# battery_buzzer_changes.net
KiCad netlist of a schematic drawn in EAGLE
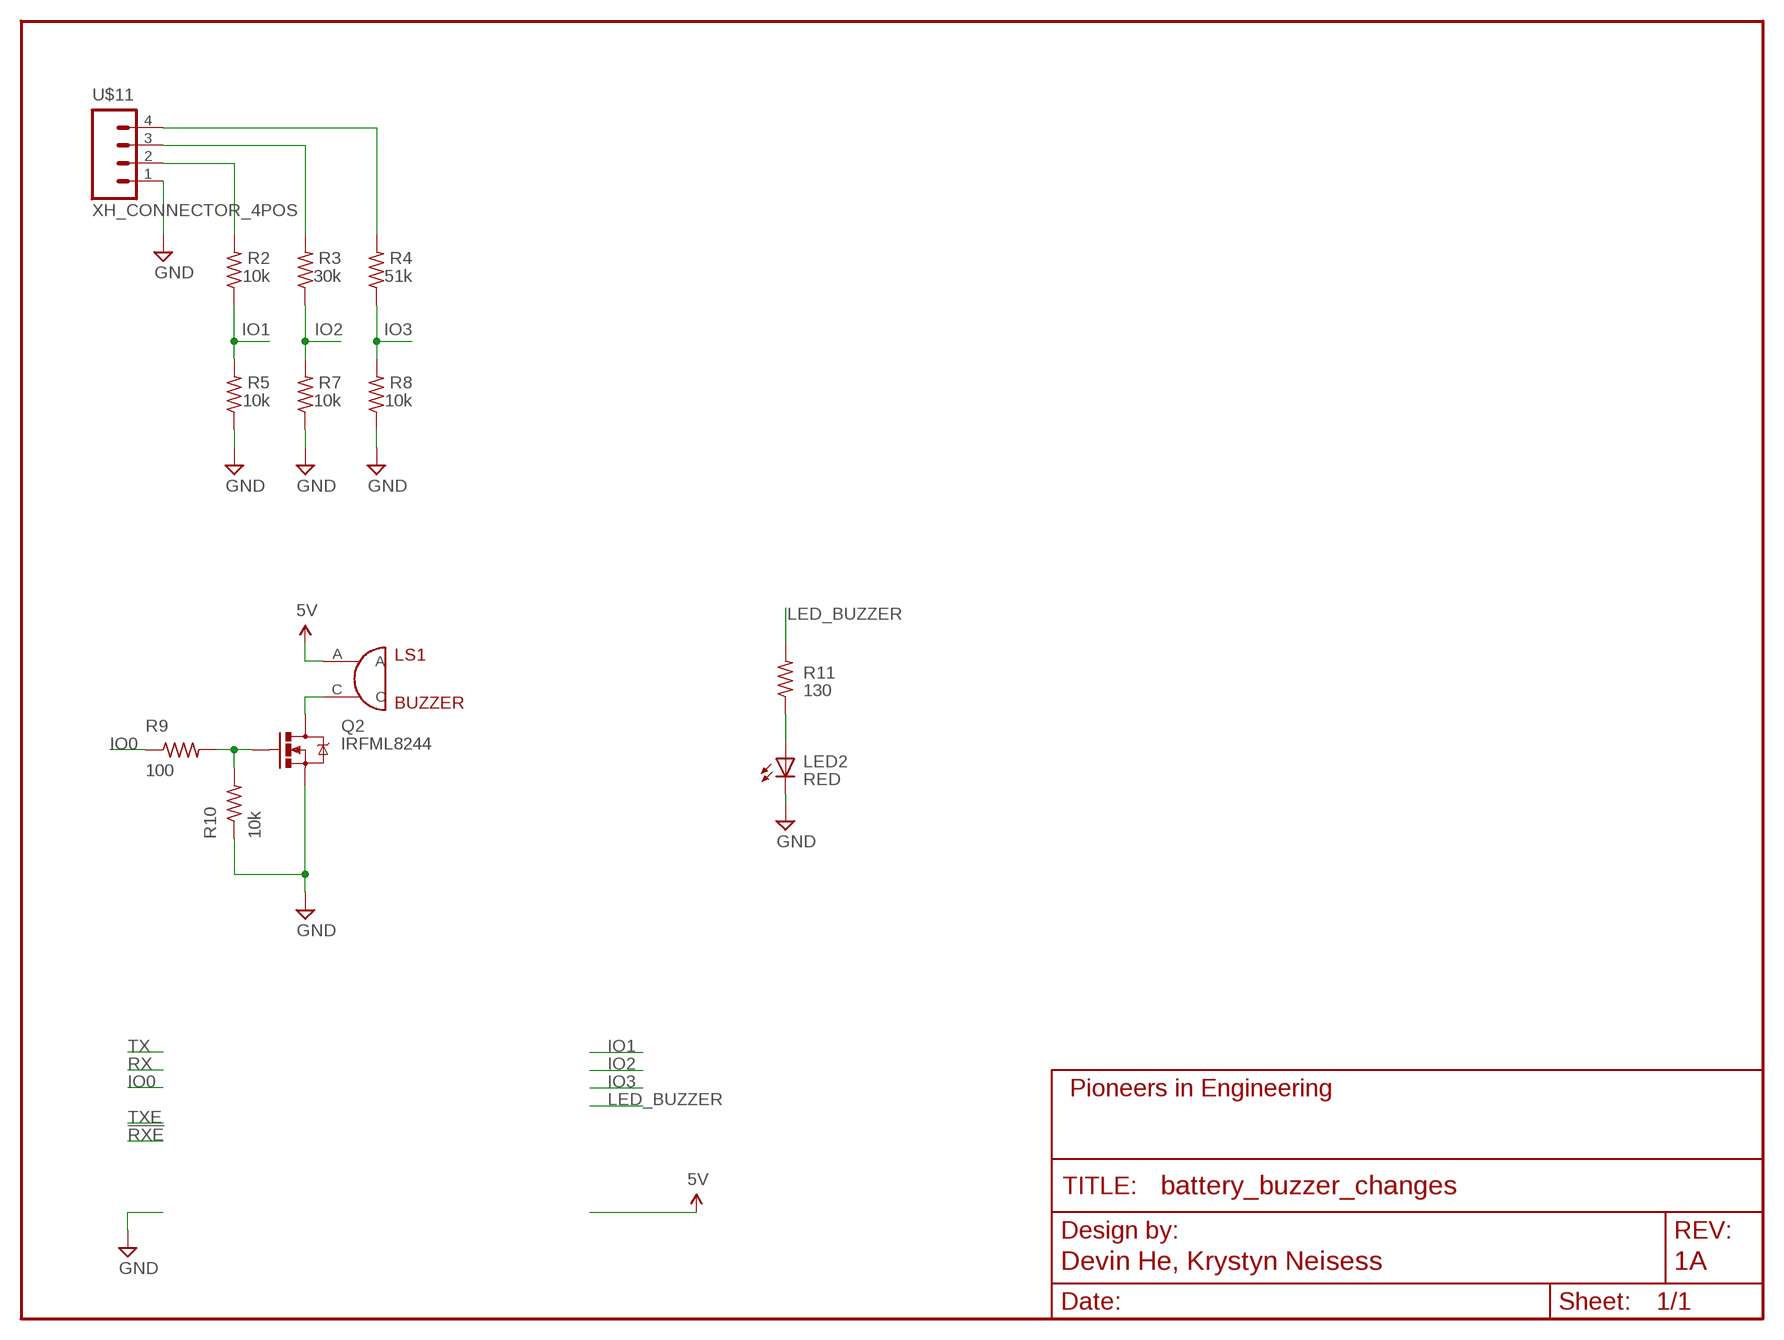
[diagram p0: schematic, sheet 1]

(export (version "E")
  (design (tool "Eeschema 10.0.6"))
  (components
    (comp (ref "LED2")
      (value "RED")
      (footprint "eagle-import:LED-0805")
      (libsource (lib "eagle-import") (part "LED0805"))
    )
    (comp (ref "LS1")
      (value "BUZZER")
      (footprint "eagle-import:BUZZER_MAGNETIC_5V_12MM_RADIAL")
      (libsource (lib "eagle-import") (part "BUZZER"))
    )
    (comp (ref "Q2")
      (value "IRFML8244")
      (footprint "eagle-import:SOT23-3")
      (libsource (lib "eagle-import") (part "MOSFET-NCHANNELSMD"))
    )
    (comp (ref "R2")
      (value "10k")
      (footprint "eagle-import:R0603")
      (libsource (lib "eagle-import") (part "R-US_R0603"))
    )
    (comp (ref "R3")
      (value "30k")
      (footprint "eagle-import:R0603")
      (libsource (lib "eagle-import") (part "R-US_R0603"))
    )
    (comp (ref "R4")
      (value "51k")
      (footprint "eagle-import:R0603")
      (libsource (lib "eagle-import") (part "R-US_R0603"))
    )
    (comp (ref "R5")
      (value "10k")
      (footprint "eagle-import:R0603")
      (libsource (lib "eagle-import") (part "R-US_R0603"))
    )
    (comp (ref "R7")
      (value "10k")
      (footprint "eagle-import:R0603")
      (libsource (lib "eagle-import") (part "R-US_R0603"))
    )
    (comp (ref "R8")
      (value "10k")
      (footprint "eagle-import:R0603")
      (libsource (lib "eagle-import") (part "R-US_R0603"))
    )
    (comp (ref "R9")
      (value "100")
      (footprint "eagle-import:R0603")
      (libsource (lib "eagle-import") (part "R-US_R0603"))
    )
    (comp (ref "R10")
      (value "10k")
      (footprint "eagle-import:R0603")
      (libsource (lib "eagle-import") (part "R-US_R0603"))
    )
    (comp (ref "R11")
      (value "130")
      (footprint "eagle-import:R0603")
      (libsource (lib "eagle-import") (part "R-US_R0603"))
    )
    (comp (ref "U$11")
      (value "XH_CONNECTOR_4POS")
      (footprint "eagle-import:XH_CONNECTOR_4POS_2.5MM")
      (libsource (lib "eagle-import") (part "XH_CONNECTOR_4POS"))
    )
  )
  (nets
    (net (code "1") (name "/IO0") (class "Default")
      (node (ref "R9") (pin "1") (pinfunction "1_1") (pintype "passive"))
    )
    (net (code "2") (name "/IO1") (class "Default")
      (node (ref "R2") (pin "1") (pinfunction "1_1") (pintype "passive"))
      (node (ref "R5") (pin "2") (pinfunction "2_2") (pintype "passive"))
    )
    (net (code "3") (name "/IO2") (class "Default")
      (node (ref "R3") (pin "1") (pinfunction "1_1") (pintype "passive"))
      (node (ref "R7") (pin "2") (pinfunction "2_2") (pintype "passive"))
    )
    (net (code "4") (name "/IO3") (class "Default")
      (node (ref "R4") (pin "1") (pinfunction "1_1") (pintype "passive"))
      (node (ref "R8") (pin "2") (pinfunction "2_2") (pintype "passive"))
    )
    (net (code "5") (name "/LED_BUZZER") (class "Default")
      (node (ref "R11") (pin "2") (pinfunction "2_2") (pintype "passive"))
    )
    (net (code "10") (name "5V") (class "Default")
      (node (ref "LS1") (pin "A") (pinfunction "A_A") (pintype "bidirectional"))
    )
    (net (code "11") (name "GND") (class "Default")
      (node (ref "LED2") (pin "C") (pinfunction "C_C") (pintype "passive"))
      (node (ref "Q2") (pin "2") (pinfunction "S_2") (pintype "passive"))
      (node (ref "R10") (pin "1") (pinfunction "1_1") (pintype "passive"))
      (node (ref "R5") (pin "1") (pinfunction "1_1") (pintype "passive"))
      (node (ref "R7") (pin "1") (pinfunction "1_1") (pintype "passive"))
      (node (ref "R8") (pin "1") (pinfunction "1_1") (pintype "passive"))
      (node (ref "U$11") (pin "1") (pinfunction "1_1") (pintype "passive"))
    )
    (net (code "12") (name "Net-(LED2-PadA)") (class "Default")
      (node (ref "LED2") (pin "A") (pinfunction "A_A") (pintype "passive"))
      (node (ref "R11") (pin "1") (pinfunction "1_1") (pintype "passive"))
    )
    (net (code "13") (name "Net-(Q2-D)") (class "Default")
      (node (ref "LS1") (pin "C") (pinfunction "C_C") (pintype "bidirectional"))
      (node (ref "Q2") (pin "3") (pinfunction "D_3") (pintype "passive"))
    )
    (net (code "14") (name "Net-(Q2-G)") (class "Default")
      (node (ref "Q2") (pin "1") (pinfunction "G_1") (pintype "passive"))
      (node (ref "R10") (pin "2") (pinfunction "2_2") (pintype "passive"))
      (node (ref "R9") (pin "2") (pinfunction "2_2") (pintype "passive"))
    )
    (net (code "15") (name "Net-(R2-Pad2)") (class "Default")
      (node (ref "R2") (pin "2") (pinfunction "2_2") (pintype "passive"))
      (node (ref "U$11") (pin "2") (pinfunction "2_2") (pintype "passive"))
    )
    (net (code "16") (name "Net-(R3-Pad2)") (class "Default")
      (node (ref "R3") (pin "2") (pinfunction "2_2") (pintype "passive"))
      (node (ref "U$11") (pin "3") (pinfunction "3_3") (pintype "passive"))
    )
    (net (code "17") (name "Net-(R4-Pad2)") (class "Default")
      (node (ref "R4") (pin "2") (pinfunction "2_2") (pintype "passive"))
      (node (ref "U$11") (pin "4") (pinfunction "4_4") (pintype "passive"))
    )
  )
)
